# ig-normal-ver13_PWM_UARTexpantion.net
KiCad netlist of a schematic drawn in EAGLE
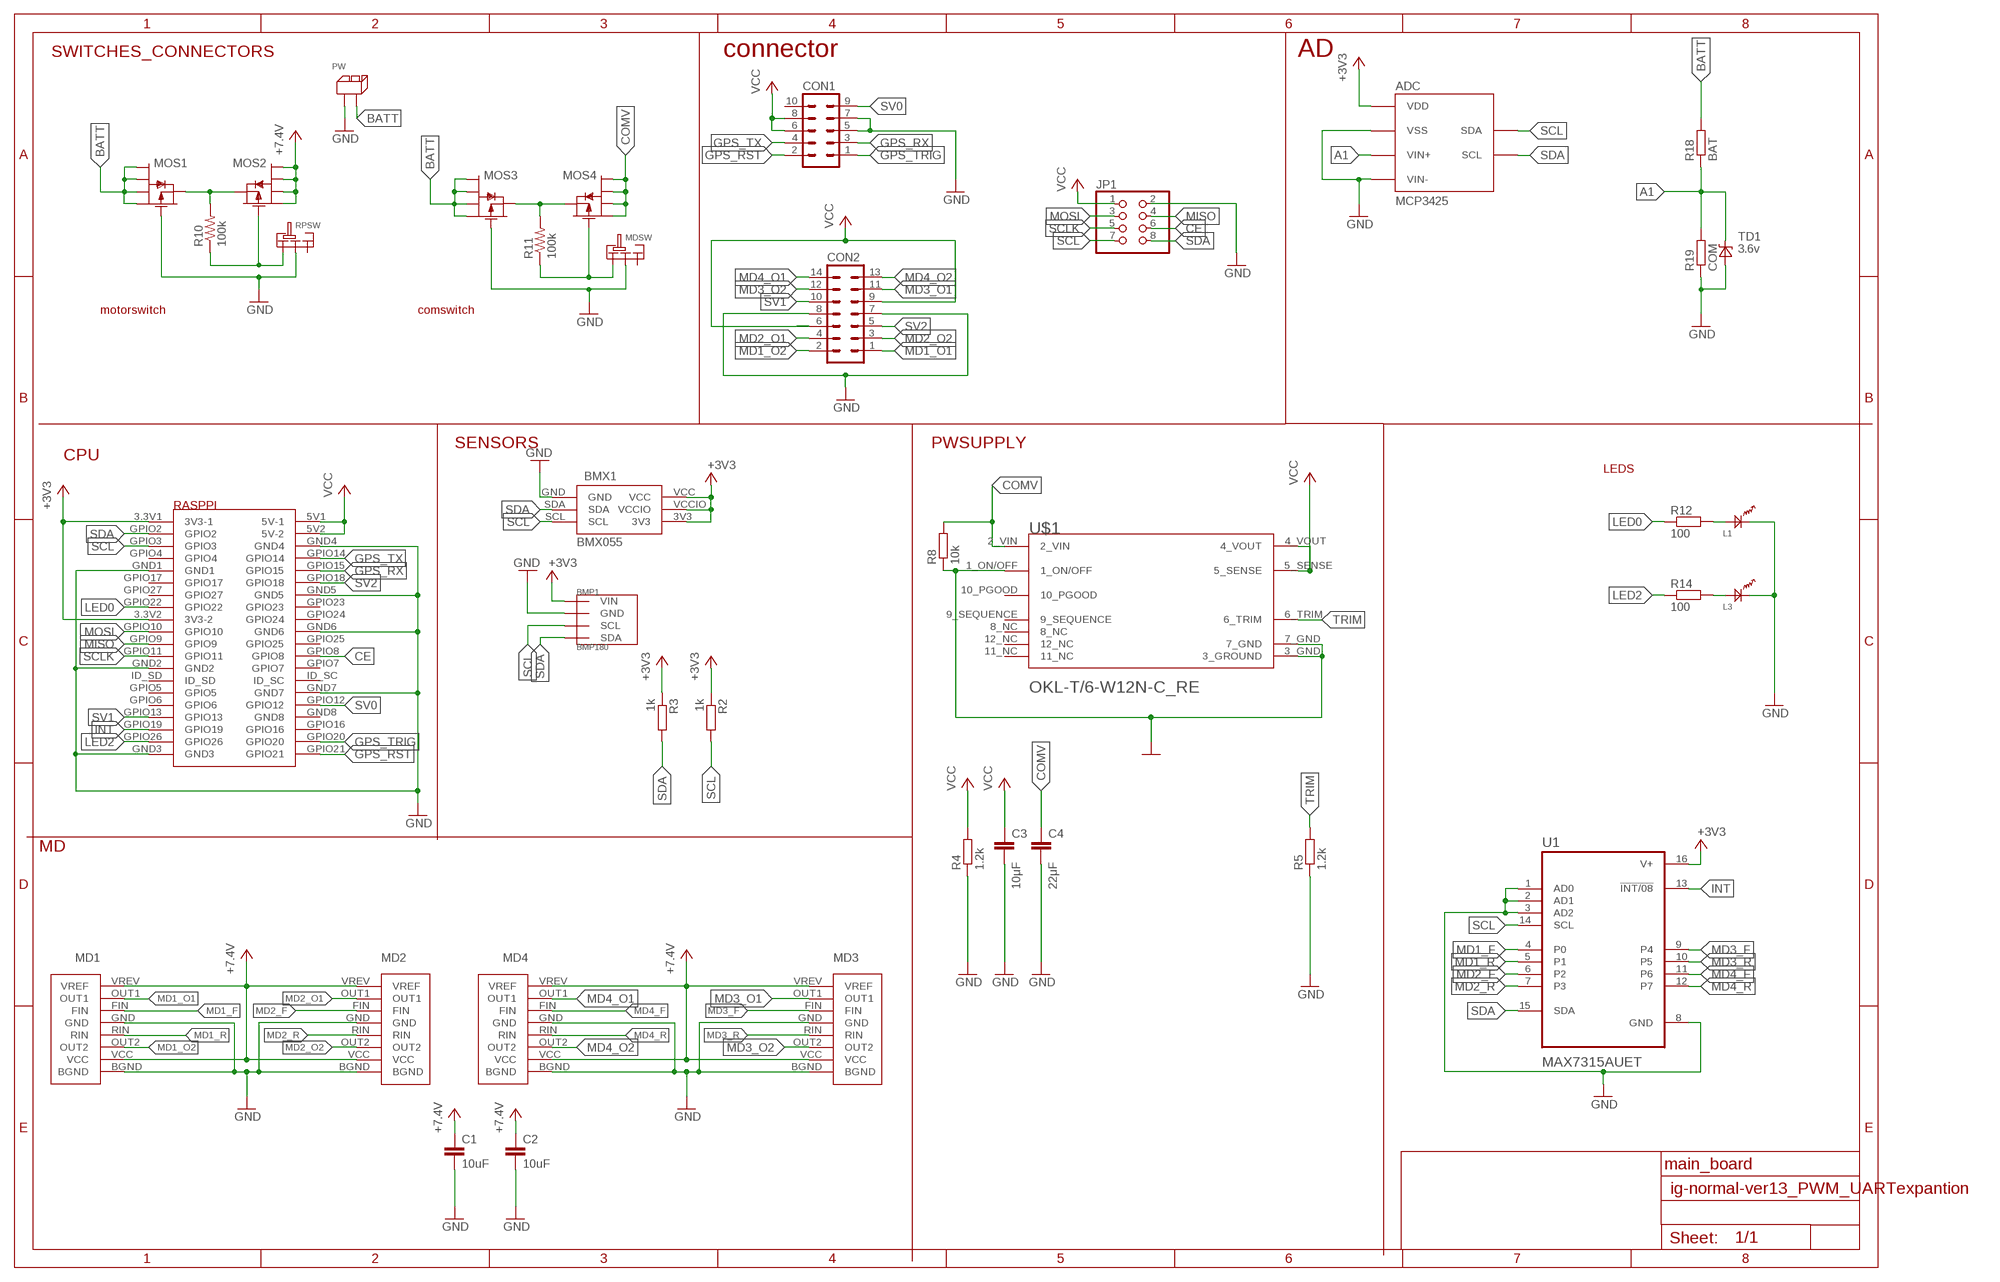
[diagram p0: schematic, sheet 1]

(export (version "E")
  (design (tool "Eeschema 10.0.6"))
  (components
    (comp (ref "ADC")
      (value "MCP3425")
      (footprint "eagle-import:SOT23-6")
      (libsource (lib "eagle-import") (part "MCP3425"))
    )
    (comp (ref "BMP1")
      (value "BMP180")
      (footprint "eagle-import:GY-68")
      (libsource (lib "eagle-import") (part "BMP180"))
    )
    (comp (ref "BMX1")
      (value "BMX055")
      (footprint "eagle-import:BMX055")
      (libsource (lib "eagle-import") (part "BMX055"))
    )
    (comp (ref "C1")
      (value "10uF")
      (footprint "eagle-import:C0603")
      (libsource (lib "eagle-import") (part "C-EUC0603"))
    )
    (comp (ref "C2")
      (value "10uF")
      (footprint "eagle-import:C0603")
      (libsource (lib "eagle-import") (part "C-EUC0603"))
    )
    (comp (ref "C3")
      (value "10μF")
      (footprint "eagle-import:C0603")
      (libsource (lib "eagle-import") (part "C-EUC0603"))
    )
    (comp (ref "C4")
      (value "22μF")
      (footprint "eagle-import:C0805")
      (libsource (lib "eagle-import") (part "C-EUC0805"))
    )
    (comp (ref "CON1")
      (value "ML10L")
      (footprint "eagle-import:ML10L")
      (libsource (lib "eagle-import") (part "ML10L"))
    )
    (comp (ref "CON2")
      (value "ML14L")
      (footprint "eagle-import:ML14L")
      (libsource (lib "eagle-import") (part "ML14L"))
    )
    (comp (ref "JP1")
      (value "PINHD-2X4")
      (footprint "eagle-import:2X04")
      (libsource (lib "eagle-import") (part "PINHD-2X4"))
    )
    (comp (ref "L1")
      (value "OSXX1608C1A")
      (footprint "eagle-import:OSXX1608C1A")
      (libsource (lib "eagle-import") (part "OSXX1608C1A"))
    )
    (comp (ref "L3")
      (value "OSXX1608C1A")
      (footprint "eagle-import:OSXX1608C1A")
      (libsource (lib "eagle-import") (part "OSXX1608C1A"))
    )
    (comp (ref "MD1")
      (value "BD6222HFP-TR")
      (footprint "eagle-import:BD6222HFP-TR")
      (libsource (lib "eagle-import") (part "BD6222HFP-TR"))
    )
    (comp (ref "MD2")
      (value "BD6222HFP-TR")
      (footprint "eagle-import:BD6222HFP-TR")
      (libsource (lib "eagle-import") (part "BD6222HFP-TR"))
    )
    (comp (ref "MD3")
      (value "BD6222HFP-TR")
      (footprint "eagle-import:BD6222HFP-TR")
      (libsource (lib "eagle-import") (part "BD6222HFP-TR"))
    )
    (comp (ref "MD4")
      (value "BD6222HFP-TR")
      (footprint "eagle-import:BD6222HFP-TR")
      (libsource (lib "eagle-import") (part "BD6222HFP-TR"))
    )
    (comp (ref "MDSW")
      (value "SRIDE_SWITCH")
      (footprint "eagle-import:SRIDE_SWITCH")
      (libsource (lib "eagle-import") (part "SRIDE_SWITCH"))
    )
    (comp (ref "MOS1")
      (value "PCH_SSM6J808R")
      (footprint "eagle-import:SSM6J808R")
      (libsource (lib "eagle-import") (part "PCH_SSM6J808R"))
    )
    (comp (ref "MOS2")
      (value "PCH_SSM6J808R")
      (footprint "eagle-import:SSM6J808R")
      (libsource (lib "eagle-import") (part "PCH_SSM6J808R"))
    )
    (comp (ref "MOS3")
      (value "PCH_SSM6J808R")
      (footprint "eagle-import:SSM6J808R")
      (libsource (lib "eagle-import") (part "PCH_SSM6J808R"))
    )
    (comp (ref "MOS4")
      (value "PCH_SSM6J808R")
      (footprint "eagle-import:SSM6J808R")
      (libsource (lib "eagle-import") (part "PCH_SSM6J808R"))
    )
    (comp (ref "PW")
      (value "2PIN")
      (footprint "eagle-import:2PIN")
      (libsource (lib "eagle-import") (part "2PIN"))
    )
    (comp (ref "R2")
      (value "1k")
      (footprint "eagle-import:R0603")
      (libsource (lib "eagle-import") (part "R-EU_R0603"))
    )
    (comp (ref "R3")
      (value "1k")
      (footprint "eagle-import:R0603")
      (libsource (lib "eagle-import") (part "R-EU_R0603"))
    )
    (comp (ref "R4")
      (value "1.2k")
      (footprint "eagle-import:R0603")
      (libsource (lib "eagle-import") (part "R-EU_R0603"))
    )
    (comp (ref "R5")
      (value "1.2k")
      (footprint "eagle-import:R0603")
      (libsource (lib "eagle-import") (part "R-EU_R0603"))
    )
    (comp (ref "R8")
      (value "10k")
      (footprint "eagle-import:R0603")
      (libsource (lib "eagle-import") (part "R-EU_R0603"))
    )
    (comp (ref "R10")
      (value "100k")
      (footprint "eagle-import:R0603")
      (libsource (lib "eagle-import") (part "R-US_R0603"))
    )
    (comp (ref "R11")
      (value "100k")
      (footprint "eagle-import:R0603")
      (libsource (lib "eagle-import") (part "R-US_R0603"))
    )
    (comp (ref "R12")
      (value "100")
      (footprint "eagle-import:R0603")
      (libsource (lib "eagle-import") (part "R-EU_R0603"))
    )
    (comp (ref "R14")
      (value "100")
      (footprint "eagle-import:R0603")
      (libsource (lib "eagle-import") (part "R-EU_R0603"))
    )
    (comp (ref "R18")
      (value "BAT")
      (footprint "eagle-import:R0603")
      (libsource (lib "eagle-import") (part "R-EU_R0603"))
    )
    (comp (ref "R19")
      (value "COM")
      (footprint "eagle-import:R0603")
      (libsource (lib "eagle-import") (part "R-EU_R0603"))
    )
    (comp (ref "RASPPI")
      (value "RASPBERYPIZEROW")
      (footprint "eagle-import:RASPBERYPIZEROW")
      (libsource (lib "eagle-import") (part "RASPBERYPIZEROW"))
    )
    (comp (ref "RPSW")
      (value "SRIDE_SWITCH")
      (footprint "eagle-import:SRIDE_SWITCH")
      (libsource (lib "eagle-import") (part "SRIDE_SWITCH"))
    )
    (comp (ref "TD1")
      (value "3.6v")
      (footprint "eagle-import:UDZV3.6V")
      (libsource (lib "eagle-import") (part "UDZV3.6B"))
    )
    (comp (ref "U$1")
      (value "OKL-T/6-W12N-C_RE")
      (footprint "eagle-import:MURATA_IKL-T-6-W12N-C_0_RECOMENDED")
      (libsource (lib "eagle-import") (part "OKL-T/6-W12N-C_RE"))
    )
    (comp (ref "U1")
      (value "MAX7315AUET")
      (footprint "eagle-import:SOP65P640X110-16N")
      (libsource (lib "eagle-import") (part "MAX7315AUET"))
    )
  )
  (nets
    (net (code "1") (name "+3V3") (class "Default")
      (node (ref "ADC") (pin "5") (pinfunction "VDD_5") (pintype "power_in"))
      (node (ref "BMP1") (pin "P1") (pinfunction "VIN_P1") (pintype "bidirectional"))
      (node (ref "BMX1") (pin "3V3") (pinfunction "3V3_3V3") (pintype "power_in"))
      (node (ref "BMX1") (pin "VCC") (pinfunction "VCC_VCC") (pintype "power_in"))
      (node (ref "BMX1") (pin "VCCIO") (pinfunction "VCCIO_VCCIO") (pintype "power_in"))
      (node (ref "R2") (pin "1") (pinfunction "1_1") (pintype "passive"))
      (node (ref "R3") (pin "1") (pinfunction "1_1") (pintype "passive"))
      (node (ref "RASPPI") (pin "3.3V1") (pinfunction "3V3-1_3.3V1") (pintype "bidirectional"))
      (node (ref "RASPPI") (pin "3.3V2") (pinfunction "3V3-2_3.3V2") (pintype "bidirectional"))
      (node (ref "U1") (pin "16") (pinfunction "V+_16") (pintype "power_in"))
    )
    (net (code "2") (name "+7.4V") (class "Default")
      (node (ref "C1") (pin "1") (pinfunction "1_1") (pintype "passive"))
      (node (ref "C2") (pin "1") (pinfunction "1_1") (pintype "passive"))
      (node (ref "MD1") (pin "VCC") (pinfunction "VCC_VCC") (pintype "bidirectional"))
      (node (ref "MD1") (pin "VREV") (pinfunction "VREF_VREV") (pintype "bidirectional"))
      (node (ref "MD2") (pin "VCC") (pinfunction "VCC_VCC") (pintype "bidirectional"))
      (node (ref "MD2") (pin "VREV") (pinfunction "VREF_VREV") (pintype "bidirectional"))
      (node (ref "MD3") (pin "VCC") (pinfunction "VCC_VCC") (pintype "bidirectional"))
      (node (ref "MD3") (pin "VREV") (pinfunction "VREF_VREV") (pintype "bidirectional"))
      (node (ref "MD4") (pin "VCC") (pinfunction "VCC_VCC") (pintype "bidirectional"))
      (node (ref "MD4") (pin "VREV") (pinfunction "VREF_VREV") (pintype "bidirectional"))
      (node (ref "MOS2") (pin "1") (pinfunction "1_1") (pintype "bidirectional"))
      (node (ref "MOS2") (pin "2") (pinfunction "2_2") (pintype "bidirectional"))
      (node (ref "MOS2") (pin "5") (pinfunction "5_5") (pintype "bidirectional"))
      (node (ref "MOS2") (pin "6") (pinfunction "6_6") (pintype "bidirectional"))
    )
    (net (code "3") (name "A1") (class "Default")
      (node (ref "ADC") (pin "1") (pinfunction "VIN+_1") (pintype "input"))
      (node (ref "R18") (pin "1") (pinfunction "1_1") (pintype "passive"))
      (node (ref "R19") (pin "2") (pinfunction "2_2") (pintype "passive"))
      (node (ref "TD1") (pin "C") (pinfunction "C_C") (pintype "bidirectional"))
    )
    (net (code "4") (name "BATT") (class "Default")
      (node (ref "MOS1") (pin "1") (pinfunction "1_1") (pintype "bidirectional"))
      (node (ref "MOS1") (pin "2") (pinfunction "2_2") (pintype "bidirectional"))
      (node (ref "MOS1") (pin "5") (pinfunction "5_5") (pintype "bidirectional"))
      (node (ref "MOS1") (pin "6") (pinfunction "6_6") (pintype "bidirectional"))
      (node (ref "MOS3") (pin "1") (pinfunction "1_1") (pintype "bidirectional"))
      (node (ref "MOS3") (pin "2") (pinfunction "2_2") (pintype "bidirectional"))
      (node (ref "MOS3") (pin "5") (pinfunction "5_5") (pintype "bidirectional"))
      (node (ref "MOS3") (pin "6") (pinfunction "6_6") (pintype "bidirectional"))
      (node (ref "PW") (pin "P$2") (pinfunction "P$2_P$2") (pintype "bidirectional"))
      (node (ref "R18") (pin "2") (pinfunction "2_2") (pintype "passive"))
    )
    (net (code "5") (name "CE") (class "Default")
      (node (ref "JP1") (pin "6") (pinfunction "6_6") (pintype "passive"))
      (node (ref "RASPPI") (pin "GPIO8") (pinfunction "GPIO8_GPIO8") (pintype "bidirectional"))
    )
    (net (code "6") (name "COMV") (class "Default")
      (node (ref "C4") (pin "1") (pinfunction "1_1") (pintype "passive"))
      (node (ref "MOS4") (pin "1") (pinfunction "1_1") (pintype "bidirectional"))
      (node (ref "MOS4") (pin "2") (pinfunction "2_2") (pintype "bidirectional"))
      (node (ref "MOS4") (pin "5") (pinfunction "5_5") (pintype "bidirectional"))
      (node (ref "MOS4") (pin "6") (pinfunction "6_6") (pintype "bidirectional"))
      (node (ref "R8") (pin "2") (pinfunction "2_2") (pintype "passive"))
      (node (ref "U$1") (pin "2_VIN") (pinfunction "2_VIN_2_VIN") (pintype "bidirectional"))
    )
    (net (code "7") (name "GND") (class "Default")
      (node (ref "ADC") (pin "2") (pinfunction "VSS_2") (pintype "power_in"))
      (node (ref "ADC") (pin "6") (pinfunction "VIN-_6") (pintype "input"))
      (node (ref "BMP1") (pin "P2") (pinfunction "GND_P2") (pintype "bidirectional"))
      (node (ref "BMX1") (pin "GND") (pinfunction "GND_GND") (pintype "power_in"))
      (node (ref "C1") (pin "2") (pinfunction "2_2") (pintype "passive"))
      (node (ref "C2") (pin "2") (pinfunction "2_2") (pintype "passive"))
      (node (ref "C3") (pin "2") (pinfunction "2_2") (pintype "passive"))
      (node (ref "C4") (pin "2") (pinfunction "2_2") (pintype "passive"))
      (node (ref "CON1") (pin "5") (pinfunction "5_5") (pintype "passive"))
      (node (ref "CON1") (pin "7") (pinfunction "7_7") (pintype "passive"))
      (node (ref "CON2") (pin "7") (pinfunction "7_7") (pintype "passive"))
      (node (ref "CON2") (pin "8") (pinfunction "8_8") (pintype "passive"))
      (node (ref "JP1") (pin "2") (pinfunction "2_2") (pintype "passive"))
      (node (ref "L1") (pin "CT") (pinfunction "CT_CT") (pintype "bidirectional"))
      (node (ref "L3") (pin "CT") (pinfunction "CT_CT") (pintype "bidirectional"))
      (node (ref "MD1") (pin "BGND") (pinfunction "BGND_BGND") (pintype "bidirectional"))
      (node (ref "MD1") (pin "GND") (pinfunction "GND_GND") (pintype "bidirectional"))
      (node (ref "MD2") (pin "BGND") (pinfunction "BGND_BGND") (pintype "bidirectional"))
      (node (ref "MD2") (pin "GND") (pinfunction "GND_GND") (pintype "bidirectional"))
      (node (ref "MD3") (pin "BGND") (pinfunction "BGND_BGND") (pintype "bidirectional"))
      (node (ref "MD3") (pin "GND") (pinfunction "GND_GND") (pintype "bidirectional"))
      (node (ref "MD4") (pin "BGND") (pinfunction "BGND_BGND") (pintype "bidirectional"))
      (node (ref "MD4") (pin "GND") (pinfunction "GND_GND") (pintype "bidirectional"))
      (node (ref "MDSW") (pin "LR") (pinfunction "LR_LR") (pintype "bidirectional"))
      (node (ref "MOS1") (pin "3") (pinfunction "3_3") (pintype "bidirectional"))
      (node (ref "MOS3") (pin "3") (pinfunction "3_3") (pintype "bidirectional"))
      (node (ref "PW") (pin "P$1") (pinfunction "P$1_P$1") (pintype "bidirectional"))
      (node (ref "R19") (pin "1") (pinfunction "1_1") (pintype "passive"))
      (node (ref "R4") (pin "1") (pinfunction "1_1") (pintype "passive"))
      (node (ref "R5") (pin "1") (pinfunction "1_1") (pintype "passive"))
      (node (ref "R8") (pin "1") (pinfunction "1_1") (pintype "passive"))
      (node (ref "RASPPI") (pin "GND1") (pinfunction "GND1_GND1") (pintype "bidirectional"))
      (node (ref "RASPPI") (pin "GND2") (pinfunction "GND2_GND2") (pintype "bidirectional"))
      (node (ref "RASPPI") (pin "GND3") (pinfunction "GND3_GND3") (pintype "bidirectional"))
      (node (ref "RASPPI") (pin "GND4") (pinfunction "GND4_GND4") (pintype "bidirectional"))
      (node (ref "RASPPI") (pin "GND5") (pinfunction "GND5_GND5") (pintype "bidirectional"))
      (node (ref "RASPPI") (pin "GND6") (pinfunction "GND6_GND6") (pintype "bidirectional"))
      (node (ref "RASPPI") (pin "GND7") (pinfunction "GND7_GND7") (pintype "bidirectional"))
      (node (ref "RPSW") (pin "LR") (pinfunction "LR_LR") (pintype "bidirectional"))
      (node (ref "TD1") (pin "A") (pinfunction "A_A") (pintype "bidirectional"))
      (node (ref "U$1") (pin "1_ON/OFF") (pinfunction "1_ON/OFF_1_ON/OFF") (pintype "bidirectional"))
      (node (ref "U$1") (pin "3_GND") (pinfunction "3_GROUND_3_GND") (pintype "power_in"))
      (node (ref "U$1") (pin "7_GND") (pinfunction "7_GND_7_GND") (pintype "power_in"))
      (node (ref "U1") (pin "1") (pinfunction "AD0_1") (pintype "input"))
      (node (ref "U1") (pin "2") (pinfunction "AD1_2") (pintype "input"))
      (node (ref "U1") (pin "3") (pinfunction "AD2_3") (pintype "input"))
      (node (ref "U1") (pin "8") (pinfunction "GND_8") (pintype "power_in"))
    )
    (net (code "8") (name "GPS_RST") (class "Default")
      (node (ref "CON1") (pin "2") (pinfunction "2_2") (pintype "passive"))
      (node (ref "RASPPI") (pin "GPIO21") (pinfunction "GPIO21_GPIO21") (pintype "bidirectional"))
    )
    (net (code "9") (name "GPS_RX") (class "Default")
      (node (ref "CON1") (pin "3") (pinfunction "3_3") (pintype "passive"))
      (node (ref "RASPPI") (pin "GPIO15") (pinfunction "GPIO15_GPIO15") (pintype "bidirectional"))
    )
    (net (code "10") (name "GPS_TRIG") (class "Default")
      (node (ref "CON1") (pin "1") (pinfunction "1_1") (pintype "passive"))
      (node (ref "RASPPI") (pin "GPIO20") (pinfunction "GPIO20_GPIO20") (pintype "bidirectional"))
    )
    (net (code "11") (name "GPS_TX") (class "Default")
      (node (ref "CON1") (pin "4") (pinfunction "4_4") (pintype "passive"))
      (node (ref "RASPPI") (pin "GPIO14") (pinfunction "GPIO14_GPIO14") (pintype "bidirectional"))
    )
    (net (code "12") (name "INT") (class "Default")
      (node (ref "RASPPI") (pin "GPIO19") (pinfunction "GPIO19_GPIO19") (pintype "bidirectional"))
      (node (ref "U1") (pin "13") (pinfunction "~{INT/08}_13") (pintype "output"))
    )
    (net (code "13") (name "LED0") (class "Default")
      (node (ref "R12") (pin "1") (pinfunction "1_1") (pintype "passive"))
      (node (ref "RASPPI") (pin "GPIO22") (pinfunction "GPIO22_GPIO22") (pintype "bidirectional"))
    )
    (net (code "14") (name "LED2") (class "Default")
      (node (ref "R14") (pin "1") (pinfunction "1_1") (pintype "passive"))
      (node (ref "RASPPI") (pin "GPIO26") (pinfunction "GPIO26_GPIO26") (pintype "bidirectional"))
    )
    (net (code "15") (name "MD1_F") (class "Default")
      (node (ref "MD1") (pin "FIN") (pinfunction "FIN_FIN") (pintype "bidirectional"))
      (node (ref "U1") (pin "4") (pinfunction "P0_4") (pintype "bidirectional"))
    )
    (net (code "16") (name "MD1_O1") (class "Default")
      (node (ref "CON2") (pin "1") (pinfunction "1_1") (pintype "passive"))
      (node (ref "MD1") (pin "OUT1") (pinfunction "OUT1_OUT1") (pintype "bidirectional"))
    )
    (net (code "17") (name "MD1_O2") (class "Default")
      (node (ref "CON2") (pin "2") (pinfunction "2_2") (pintype "passive"))
      (node (ref "MD1") (pin "OUT2") (pinfunction "OUT2_OUT2") (pintype "bidirectional"))
    )
    (net (code "18") (name "MD1_R") (class "Default")
      (node (ref "MD1") (pin "RIN") (pinfunction "RIN_RIN") (pintype "bidirectional"))
      (node (ref "U1") (pin "5") (pinfunction "P1_5") (pintype "bidirectional"))
    )
    (net (code "19") (name "MD2_F") (class "Default")
      (node (ref "MD2") (pin "FIN") (pinfunction "FIN_FIN") (pintype "bidirectional"))
      (node (ref "U1") (pin "6") (pinfunction "P2_6") (pintype "bidirectional"))
    )
    (net (code "20") (name "MD2_O1") (class "Default")
      (node (ref "CON2") (pin "4") (pinfunction "4_4") (pintype "passive"))
      (node (ref "MD2") (pin "OUT1") (pinfunction "OUT1_OUT1") (pintype "bidirectional"))
    )
    (net (code "21") (name "MD2_O2") (class "Default")
      (node (ref "CON2") (pin "3") (pinfunction "3_3") (pintype "passive"))
      (node (ref "MD2") (pin "OUT2") (pinfunction "OUT2_OUT2") (pintype "bidirectional"))
    )
    (net (code "22") (name "MD2_R") (class "Default")
      (node (ref "MD2") (pin "RIN") (pinfunction "RIN_RIN") (pintype "bidirectional"))
      (node (ref "U1") (pin "7") (pinfunction "P3_7") (pintype "bidirectional"))
    )
    (net (code "23") (name "MD3_F") (class "Default")
      (node (ref "MD3") (pin "FIN") (pinfunction "FIN_FIN") (pintype "bidirectional"))
      (node (ref "U1") (pin "9") (pinfunction "P4_9") (pintype "bidirectional"))
    )
    (net (code "24") (name "MD3_O1") (class "Default")
      (node (ref "CON2") (pin "11") (pinfunction "11_11") (pintype "passive"))
      (node (ref "MD3") (pin "OUT1") (pinfunction "OUT1_OUT1") (pintype "bidirectional"))
    )
    (net (code "25") (name "MD3_O2") (class "Default")
      (node (ref "CON2") (pin "12") (pinfunction "12_12") (pintype "passive"))
      (node (ref "MD3") (pin "OUT2") (pinfunction "OUT2_OUT2") (pintype "bidirectional"))
    )
    (net (code "26") (name "MD3_R") (class "Default")
      (node (ref "MD3") (pin "RIN") (pinfunction "RIN_RIN") (pintype "bidirectional"))
      (node (ref "U1") (pin "10") (pinfunction "P5_10") (pintype "bidirectional"))
    )
    (net (code "27") (name "MD4_F") (class "Default")
      (node (ref "MD4") (pin "FIN") (pinfunction "FIN_FIN") (pintype "bidirectional"))
      (node (ref "U1") (pin "11") (pinfunction "P6_11") (pintype "bidirectional"))
    )
    (net (code "28") (name "MD4_O1") (class "Default")
      (node (ref "CON2") (pin "14") (pinfunction "14_14") (pintype "passive"))
      (node (ref "MD4") (pin "OUT1") (pinfunction "OUT1_OUT1") (pintype "bidirectional"))
    )
    (net (code "29") (name "MD4_O2") (class "Default")
      (node (ref "CON2") (pin "13") (pinfunction "13_13") (pintype "passive"))
      (node (ref "MD4") (pin "OUT2") (pinfunction "OUT2_OUT2") (pintype "bidirectional"))
    )
    (net (code "30") (name "MD4_R") (class "Default")
      (node (ref "MD4") (pin "RIN") (pinfunction "RIN_RIN") (pintype "bidirectional"))
      (node (ref "U1") (pin "12") (pinfunction "P7_12") (pintype "bidirectional"))
    )
    (net (code "31") (name "MISO") (class "Default")
      (node (ref "JP1") (pin "4") (pinfunction "4_4") (pintype "passive"))
      (node (ref "RASPPI") (pin "GPIO9") (pinfunction "GPIO9_GPIO9") (pintype "bidirectional"))
    )
    (net (code "32") (name "MOSI") (class "Default")
      (node (ref "JP1") (pin "3") (pinfunction "3_3") (pintype "passive"))
      (node (ref "RASPPI") (pin "GPIO10") (pinfunction "GPIO10_GPIO10") (pintype "bidirectional"))
    )
    (net (code "33") (name "Net-(L1-PadAN)") (class "Default")
      (node (ref "L1") (pin "AN") (pinfunction "AN_AN") (pintype "bidirectional"))
      (node (ref "R12") (pin "2") (pinfunction "2_2") (pintype "passive"))
    )
    (net (code "34") (name "Net-(L3-PadAN)") (class "Default")
      (node (ref "L3") (pin "AN") (pinfunction "AN_AN") (pintype "bidirectional"))
      (node (ref "R14") (pin "2") (pinfunction "2_2") (pintype "passive"))
    )
    (net (code "35") (name "Net-(MDSW-PadL)") (class "Default")
      (node (ref "MDSW") (pin "L") (pinfunction "L_L") (pintype "bidirectional"))
      (node (ref "MOS4") (pin "3") (pinfunction "3_3") (pintype "bidirectional"))
      (node (ref "R11") (pin "1") (pinfunction "1_1") (pintype "passive"))
    )
    (net (code "36") (name "Net-(MOS1-Pad4)") (class "Default")
      (node (ref "MOS1") (pin "4") (pinfunction "4_4") (pintype "bidirectional"))
      (node (ref "MOS2") (pin "4") (pinfunction "4_4") (pintype "bidirectional"))
      (node (ref "R10") (pin "2") (pinfunction "2_2") (pintype "passive"))
    )
    (net (code "37") (name "Net-(MOS2-Pad3)") (class "Default")
      (node (ref "MOS2") (pin "3") (pinfunction "3_3") (pintype "bidirectional"))
      (node (ref "R10") (pin "1") (pinfunction "1_1") (pintype "passive"))
      (node (ref "RPSW") (pin "L") (pinfunction "L_L") (pintype "bidirectional"))
    )
    (net (code "38") (name "Net-(MOS3-Pad4)") (class "Default")
      (node (ref "MOS3") (pin "4") (pinfunction "4_4") (pintype "bidirectional"))
      (node (ref "MOS4") (pin "4") (pinfunction "4_4") (pintype "bidirectional"))
      (node (ref "R11") (pin "2") (pinfunction "2_2") (pintype "passive"))
    )
    (net (code "39") (name "SCL") (class "Default")
      (node (ref "ADC") (pin "4") (pinfunction "SDA_4") (pintype "bidirectional"))
      (node (ref "BMP1") (pin "P3") (pinfunction "SCL_P3") (pintype "bidirectional"))
      (node (ref "BMX1") (pin "SCL") (pinfunction "SCL_SCL") (pintype "bidirectional"))
      (node (ref "JP1") (pin "7") (pinfunction "7_7") (pintype "passive"))
      (node (ref "R2") (pin "2") (pinfunction "2_2") (pintype "passive"))
      (node (ref "RASPPI") (pin "GPIO3") (pinfunction "GPIO3_GPIO3") (pintype "bidirectional"))
      (node (ref "U1") (pin "14") (pinfunction "SCL_14") (pintype "input"))
    )
    (net (code "40") (name "SCLK") (class "Default")
      (node (ref "JP1") (pin "5") (pinfunction "5_5") (pintype "passive"))
      (node (ref "RASPPI") (pin "GPIO11") (pinfunction "GPIO11_GPIO11") (pintype "bidirectional"))
    )
    (net (code "41") (name "SDA") (class "Default")
      (node (ref "ADC") (pin "3") (pinfunction "SCL_3") (pintype "bidirectional"))
      (node (ref "BMP1") (pin "P4") (pinfunction "SDA_P4") (pintype "bidirectional"))
      (node (ref "BMX1") (pin "SDA") (pinfunction "SDA_SDA") (pintype "bidirectional"))
      (node (ref "JP1") (pin "8") (pinfunction "8_8") (pintype "passive"))
      (node (ref "R3") (pin "2") (pinfunction "2_2") (pintype "passive"))
      (node (ref "RASPPI") (pin "GPIO2") (pinfunction "GPIO2_GPIO2") (pintype "bidirectional"))
      (node (ref "U1") (pin "15") (pinfunction "SDA_15") (pintype "bidirectional"))
    )
    (net (code "42") (name "SV0") (class "Default")
      (node (ref "CON1") (pin "9") (pinfunction "9_9") (pintype "passive"))
      (node (ref "RASPPI") (pin "GPIO12") (pinfunction "GPIO12_GPIO12") (pintype "bidirectional"))
    )
    (net (code "43") (name "SV1") (class "Default")
      (node (ref "CON2") (pin "10") (pinfunction "10_10") (pintype "passive"))
      (node (ref "RASPPI") (pin "GPIO13") (pinfunction "GPIO13_GPIO13") (pintype "bidirectional"))
    )
    (net (code "44") (name "SV2") (class "Default")
      (node (ref "CON2") (pin "5") (pinfunction "5_5") (pintype "passive"))
      (node (ref "RASPPI") (pin "GPIO18") (pinfunction "GPIO18_GPIO18") (pintype "bidirectional"))
    )
    (net (code "45") (name "TRIM") (class "Default")
      (node (ref "R5") (pin "2") (pinfunction "2_2") (pintype "passive"))
      (node (ref "U$1") (pin "6_TRIM") (pinfunction "6_TRIM_6_TRIM") (pintype "passive"))
    )
    (net (code "46") (name "VCC") (class "Default")
      (node (ref "C3") (pin "1") (pinfunction "1_1") (pintype "passive"))
      (node (ref "CON1") (pin "6") (pinfunction "6_6") (pintype "passive"))
      (node (ref "CON1") (pin "8") (pinfunction "8_8") (pintype "passive"))
      (node (ref "CON2") (pin "6") (pinfunction "6_6") (pintype "passive"))
      (node (ref "CON2") (pin "9") (pinfunction "9_9") (pintype "passive"))
      (node (ref "JP1") (pin "1") (pinfunction "1_1") (pintype "passive"))
      (node (ref "R4") (pin "2") (pinfunction "2_2") (pintype "passive"))
      (node (ref "RASPPI") (pin "5V1") (pinfunction "5V-1_5V1") (pintype "bidirectional"))
      (node (ref "RASPPI") (pin "5V2") (pinfunction "5V-2_5V2") (pintype "bidirectional"))
      (node (ref "U$1") (pin "4_VOUT") (pinfunction "4_VOUT_4_VOUT") (pintype "bidirectional"))
      (node (ref "U$1") (pin "5_SENSE") (pinfunction "5_SENSE_5_SENSE") (pintype "passive"))
    )
    (net (code "47") (name "unconnected-(CON1-Pad10)") (class "Default")
      (node (ref "CON1") (pin "10") (pinfunction "10_10") (pintype "passive"))
    )
    (net (code "48") (name "unconnected-(MDSW-PadR)") (class "Default")
      (node (ref "MDSW") (pin "R") (pinfunction "R_R") (pintype "bidirectional"))
    )
    (net (code "49") (name "unconnected-(RASPPI-PadGND8)") (class "Default")
      (node (ref "RASPPI") (pin "GND8") (pinfunction "GND8_GND8") (pintype "bidirectional"))
    )
    (net (code "50") (name "unconnected-(RASPPI-PadGPIO4)") (class "Default")
      (node (ref "RASPPI") (pin "GPIO4") (pinfunction "GPIO4_GPIO4") (pintype "bidirectional"))
    )
    (net (code "51") (name "unconnected-(RASPPI-PadGPIO5)") (class "Default")
      (node (ref "RASPPI") (pin "GPIO5") (pinfunction "GPIO5_GPIO5") (pintype "bidirectional"))
    )
    (net (code "52") (name "unconnected-(RASPPI-PadGPIO6)") (class "Default")
      (node (ref "RASPPI") (pin "GPIO6") (pinfunction "GPIO6_GPIO6") (pintype "bidirectional"))
    )
    (net (code "53") (name "unconnected-(RASPPI-PadGPIO7)") (class "Default")
      (node (ref "RASPPI") (pin "GPIO7") (pinfunction "GPIO7_GPIO7") (pintype "bidirectional"))
    )
    (net (code "54") (name "unconnected-(RASPPI-PadGPIO16)") (class "Default")
      (node (ref "RASPPI") (pin "GPIO16") (pinfunction "GPIO16_GPIO16") (pintype "bidirectional"))
    )
    (net (code "55") (name "unconnected-(RASPPI-PadGPIO17)") (class "Default")
      (node (ref "RASPPI") (pin "GPIO17") (pinfunction "GPIO17_GPIO17") (pintype "bidirectional"))
    )
    (net (code "56") (name "unconnected-(RASPPI-PadGPIO23)") (class "Default")
      (node (ref "RASPPI") (pin "GPIO23") (pinfunction "GPIO23_GPIO23") (pintype "bidirectional"))
    )
    (net (code "57") (name "unconnected-(RASPPI-PadGPIO24)") (class "Default")
      (node (ref "RASPPI") (pin "GPIO24") (pinfunction "GPIO24_GPIO24") (pintype "bidirectional"))
    )
    (net (code "58") (name "unconnected-(RASPPI-PadGPIO25)") (class "Default")
      (node (ref "RASPPI") (pin "GPIO25") (pinfunction "GPIO25_GPIO25") (pintype "bidirectional"))
    )
    (net (code "59") (name "unconnected-(RASPPI-PadGPIO27)") (class "Default")
      (node (ref "RASPPI") (pin "GPIO27") (pinfunction "GPIO27_GPIO27") (pintype "bidirectional"))
    )
    (net (code "60") (name "unconnected-(RASPPI-PadID_SC)") (class "Default")
      (node (ref "RASPPI") (pin "ID_SC") (pinfunction "ID_SC_ID_SC") (pintype "bidirectional"))
    )
    (net (code "61") (name "unconnected-(RASPPI-PadID_SD)") (class "Default")
      (node (ref "RASPPI") (pin "ID_SD") (pinfunction "ID_SD_ID_SD") (pintype "bidirectional"))
    )
    (net (code "62") (name "unconnected-(RPSW-PadR)") (class "Default")
      (node (ref "RPSW") (pin "R") (pinfunction "R_R") (pintype "bidirectional"))
    )
    (net (code "63") (name "unconnected-(U$1-Pad8_NC)") (class "Default")
      (node (ref "U$1") (pin "8_NC") (pinfunction "8_NC_8_NC") (pintype "passive"))
    )
    (net (code "64") (name "unconnected-(U$1-Pad9_SEQUENCE)") (class "Default")
      (node (ref "U$1") (pin "9_SEQUENCE") (pinfunction "9_SEQUENCE_9_SEQUENCE") (pintype "passive"))
    )
    (net (code "65") (name "unconnected-(U$1-Pad10_PGOOD)") (class "Default")
      (node (ref "U$1") (pin "10_PGOOD") (pinfunction "10_PGOOD_10_PGOOD") (pintype "open_collector"))
    )
    (net (code "66") (name "unconnected-(U$1-Pad11_NC)") (class "Default")
      (node (ref "U$1") (pin "11_NC") (pinfunction "11_NC_11_NC") (pintype "passive"))
    )
    (net (code "67") (name "unconnected-(U$1-Pad12_NC)") (class "Default")
      (node (ref "U$1") (pin "12_NC") (pinfunction "12_NC_12_NC") (pintype "passive"))
    )
  )
)
